# power-board.net
KiCad netlist of a schematic drawn in EAGLE
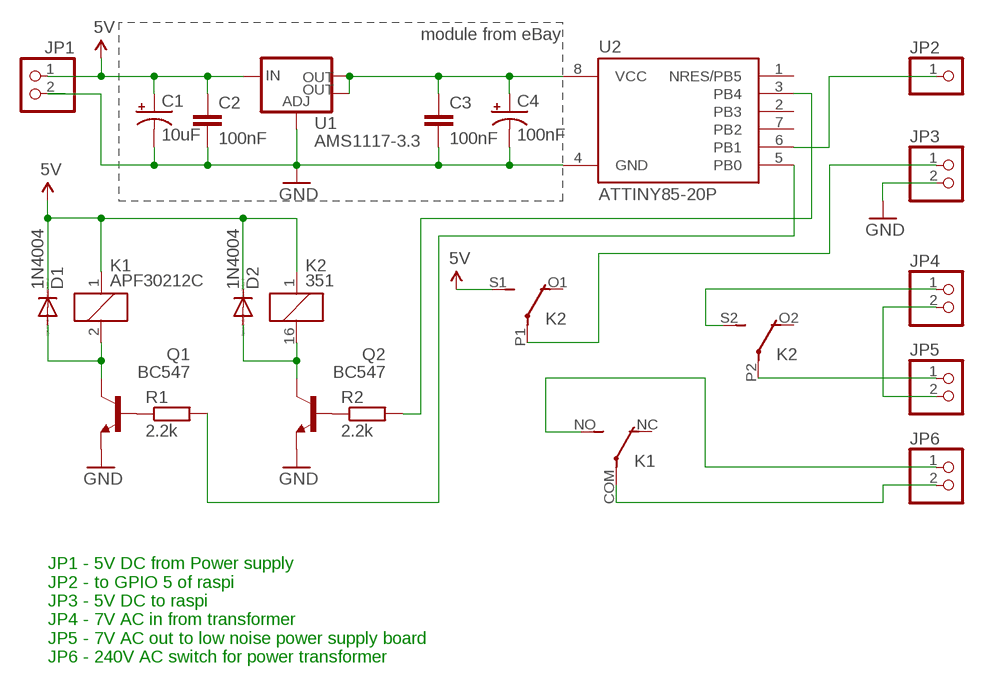
[diagram p0: schematic, sheet 1]

(export (version "E")
  (design (tool "Eeschema 10.0.6"))
  (components
    (comp (ref "C1")
      (value "10uF")
      (footprint "eagle-import:CPOL-RADIAL-10UF-25V-KIT")
      (libsource (lib "eagle-import") (part "10UF-25V-20%(PTH)KIT"))
    )
    (comp (ref "C2")
      (value "100nF")
      (footprint "eagle-import:0402-CAP")
      (libsource (lib "eagle-import") (part "CAP0402-CAP"))
    )
    (comp (ref "C3")
      (value "100nF")
      (footprint "eagle-import:0402-CAP")
      (libsource (lib "eagle-import") (part "CAP0402-CAP"))
    )
    (comp (ref "C4")
      (value "100nF")
      (footprint "eagle-import:CPOL-RADIAL-10UF-25V-KIT")
      (libsource (lib "eagle-import") (part "10UF-25V-20%(PTH)KIT"))
    )
    (comp (ref "D1")
      (value "1N4004")
      (footprint "eagle-import:DO41-10")
      (libsource (lib "eagle-import") (part "1N4004"))
    )
    (comp (ref "D2")
      (value "1N4004")
      (footprint "eagle-import:DO41-10")
      (libsource (lib "eagle-import") (part "1N4004"))
    )
    (comp (ref "JP1")
      (value "PINHD-1X2")
      (footprint "eagle-import:1X02")
      (libsource (lib "eagle-import") (part "PINHD-1X2"))
    )
    (comp (ref "JP2")
      (value "PINHD-1X1")
      (footprint "eagle-import:1X01")
      (libsource (lib "eagle-import") (part "PINHD-1X1"))
    )
    (comp (ref "JP3")
      (value "PINHD-1X2")
      (footprint "eagle-import:1X02")
      (libsource (lib "eagle-import") (part "PINHD-1X2"))
    )
    (comp (ref "JP4")
      (value "PINHD-1X2")
      (footprint "eagle-import:1X02")
      (libsource (lib "eagle-import") (part "PINHD-1X2"))
    )
    (comp (ref "JP5")
      (value "PINHD-1X2")
      (footprint "eagle-import:1X02")
      (libsource (lib "eagle-import") (part "PINHD-1X2"))
    )
    (comp (ref "JP6")
      (value "PINHD-1X2")
      (footprint "eagle-import:1X02")
      (libsource (lib "eagle-import") (part "PINHD-1X2"))
    )
    (comp (ref "K1")
      (value "APF30212C")
      (footprint "eagle-import:APF30212C")
      (libsource (lib "eagle-import") (part "APF30212C"))
    )
    (comp (ref "K2")
      (value "351")
      (footprint "eagle-import:351")
      (libsource (lib "eagle-import") (part "351"))
    )
    (comp (ref "Q1")
      (value "BC547")
      (footprint "eagle-import:TO92")
      (libsource (lib "eagle-import") (part "BC547"))
    )
    (comp (ref "Q2")
      (value "BC547")
      (footprint "eagle-import:TO92")
      (libsource (lib "eagle-import") (part "BC547"))
    )
    (comp (ref "R1")
      (value "2.2k")
      (footprint "eagle-import:0204_7")
      (libsource (lib "eagle-import") (part "R-EU_0204/7"))
    )
    (comp (ref "R2")
      (value "2.2k")
      (footprint "eagle-import:0204_7")
      (libsource (lib "eagle-import") (part "R-EU_0204/7"))
    )
    (comp (ref "U1")
      (value "AMS1117-3.3")
      (footprint "eagle-import:SOT223")
      (libsource (lib "eagle-import") (part "V_REG_LM1117SOT223"))
    )
    (comp (ref "U2")
      (value "ATTINY85-20P")
      (footprint "eagle-import:PDIP08_300MIL")
      (libsource (lib "eagle-import") (part "ATTINY85P-20"))
    )
  )
  (nets
    (net (code "1") (name "5V") (class "Default")
      (node (ref "C1") (pin "1") (pinfunction "+_1") (pintype "passive"))
      (node (ref "C2") (pin "1") (pinfunction "1_1") (pintype "passive"))
      (node (ref "D1") (pin "C") (pinfunction "C_C") (pintype "passive"))
      (node (ref "D2") (pin "C") (pinfunction "C_C") (pintype "passive"))
      (node (ref "JP1") (pin "1") (pinfunction "1_1") (pintype "passive"))
      (node (ref "K1") (pin "1") (pinfunction "1_1") (pintype "passive"))
      (node (ref "K2") (pin "1") (pinfunction "1_1") (pintype "passive"))
      (node (ref "K2") (pin "S1") (pinfunction "S_S1") (pintype "passive"))
      (node (ref "U1") (pin "3") (pinfunction "IN_3") (pintype "input"))
    )
    (net (code "2") (name "GND") (class "Default")
      (node (ref "C1") (pin "2") (pinfunction "-_2") (pintype "passive"))
      (node (ref "C2") (pin "2") (pinfunction "2_2") (pintype "passive"))
      (node (ref "C3") (pin "2") (pinfunction "2_2") (pintype "passive"))
      (node (ref "C4") (pin "2") (pinfunction "-_2") (pintype "passive"))
      (node (ref "JP1") (pin "2") (pinfunction "2_2") (pintype "passive"))
      (node (ref "JP3") (pin "2") (pinfunction "2_2") (pintype "passive"))
      (node (ref "Q1") (pin "1") (pinfunction "E_1") (pintype "passive"))
      (node (ref "Q2") (pin "1") (pinfunction "E_1") (pintype "passive"))
      (node (ref "U1") (pin "1") (pinfunction "ADJ_1") (pintype "input"))
      (node (ref "U2") (pin "4") (pinfunction "GND_4") (pintype "power_in"))
    )
    (net (code "3") (name "Net-(C4-+)") (class "Default")
      (node (ref "C3") (pin "1") (pinfunction "1_1") (pintype "passive"))
      (node (ref "C4") (pin "1") (pinfunction "+_1") (pintype "passive"))
      (node (ref "U1") (pin "2") (pinfunction "OUT_2") (pintype "output"))
      (node (ref "U1") (pin "4") (pinfunction "OUT_4") (pintype "output"))
      (node (ref "U2") (pin "8") (pinfunction "VCC_8") (pintype "power_in"))
    )
    (net (code "4") (name "Net-(JP4-Pad2)") (class "Default")
      (node (ref "JP4") (pin "2") (pinfunction "2_2") (pintype "passive"))
      (node (ref "JP5") (pin "2") (pinfunction "2_2") (pintype "passive"))
    )
    (net (code "5") (name "Net-(K1B-P)") (class "Default")
      (node (ref "JP6") (pin "2") (pinfunction "2_2") (pintype "passive"))
      (node (ref "K1") (pin "COM") (pinfunction "P_COM") (pintype "passive"))
    )
    (net (code "6") (name "Net-(K1B-S)") (class "Default")
      (node (ref "JP6") (pin "1") (pinfunction "1_1") (pintype "passive"))
      (node (ref "K1") (pin "NO") (pinfunction "S_NO") (pintype "passive"))
    )
    (net (code "7") (name "Net-(K2A-2)") (class "Default")
      (node (ref "D2") (pin "A") (pinfunction "A_A") (pintype "passive"))
      (node (ref "K2") (pin "16") (pinfunction "2_16") (pintype "passive"))
      (node (ref "Q2") (pin "3") (pinfunction "C_3") (pintype "passive"))
    )
    (net (code "8") (name "Net-(K2B-P)") (class "Default")
      (node (ref "JP3") (pin "1") (pinfunction "1_1") (pintype "passive"))
      (node (ref "K2") (pin "P1") (pinfunction "P_P1") (pintype "passive"))
    )
    (net (code "9") (name "Net-(K2C-P)") (class "Default")
      (node (ref "JP5") (pin "1") (pinfunction "1_1") (pintype "passive"))
      (node (ref "K2") (pin "P2") (pinfunction "P_P2") (pintype "passive"))
    )
    (net (code "10") (name "Net-(K2C-S)") (class "Default")
      (node (ref "JP4") (pin "1") (pinfunction "1_1") (pintype "passive"))
      (node (ref "K2") (pin "S2") (pinfunction "S_S2") (pintype "passive"))
    )
    (net (code "11") (name "Net-(Q1-B)") (class "Default")
      (node (ref "Q1") (pin "2") (pinfunction "B_2") (pintype "passive"))
      (node (ref "R1") (pin "1") (pinfunction "1_1") (pintype "passive"))
    )
    (net (code "12") (name "Net-(Q1-C)") (class "Default")
      (node (ref "D1") (pin "A") (pinfunction "A_A") (pintype "passive"))
      (node (ref "K1") (pin "2") (pinfunction "2_2") (pintype "passive"))
      (node (ref "Q1") (pin "3") (pinfunction "C_3") (pintype "passive"))
    )
    (net (code "13") (name "Net-(Q2-B)") (class "Default")
      (node (ref "Q2") (pin "2") (pinfunction "B_2") (pintype "passive"))
      (node (ref "R2") (pin "1") (pinfunction "1_1") (pintype "passive"))
    )
    (net (code "14") (name "Net-(U2-PB0)") (class "Default")
      (node (ref "R1") (pin "2") (pinfunction "2_2") (pintype "passive"))
      (node (ref "U2") (pin "5") (pinfunction "PB0_5") (pintype "bidirectional"))
    )
    (net (code "15") (name "Net-(U2-PB1)") (class "Default")
      (node (ref "JP2") (pin "1") (pinfunction "1_1") (pintype "passive"))
      (node (ref "U2") (pin "6") (pinfunction "PB1_6") (pintype "bidirectional"))
    )
    (net (code "16") (name "Net-(U2-PB4)") (class "Default")
      (node (ref "R2") (pin "2") (pinfunction "2_2") (pintype "passive"))
      (node (ref "U2") (pin "3") (pinfunction "PB4_3") (pintype "bidirectional"))
    )
    (net (code "17") (name "unconnected-(K1B-O-PadNC)") (class "Default")
      (node (ref "K1") (pin "NC") (pinfunction "O_NC") (pintype "passive"))
    )
    (net (code "18") (name "unconnected-(K2B-O-PadO1)") (class "Default")
      (node (ref "K2") (pin "O1") (pinfunction "O_O1") (pintype "passive"))
    )
    (net (code "19") (name "unconnected-(K2C-O-PadO2)") (class "Default")
      (node (ref "K2") (pin "O2") (pinfunction "O_O2") (pintype "passive"))
    )
    (net (code "20") (name "unconnected-(U2-NRES{slash}PB5-Pad1)") (class "Default")
      (node (ref "U2") (pin "1") (pinfunction "NRES/PB5_1") (pintype "bidirectional"))
    )
    (net (code "21") (name "unconnected-(U2-PB2-Pad7)") (class "Default")
      (node (ref "U2") (pin "7") (pinfunction "PB2_7") (pintype "bidirectional"))
    )
    (net (code "22") (name "unconnected-(U2-PB3-Pad2)") (class "Default")
      (node (ref "U2") (pin "2") (pinfunction "PB3_2") (pintype "bidirectional"))
    )
  )
)
